# hr_monitor.net
KiCad netlist of a schematic drawn in EAGLE
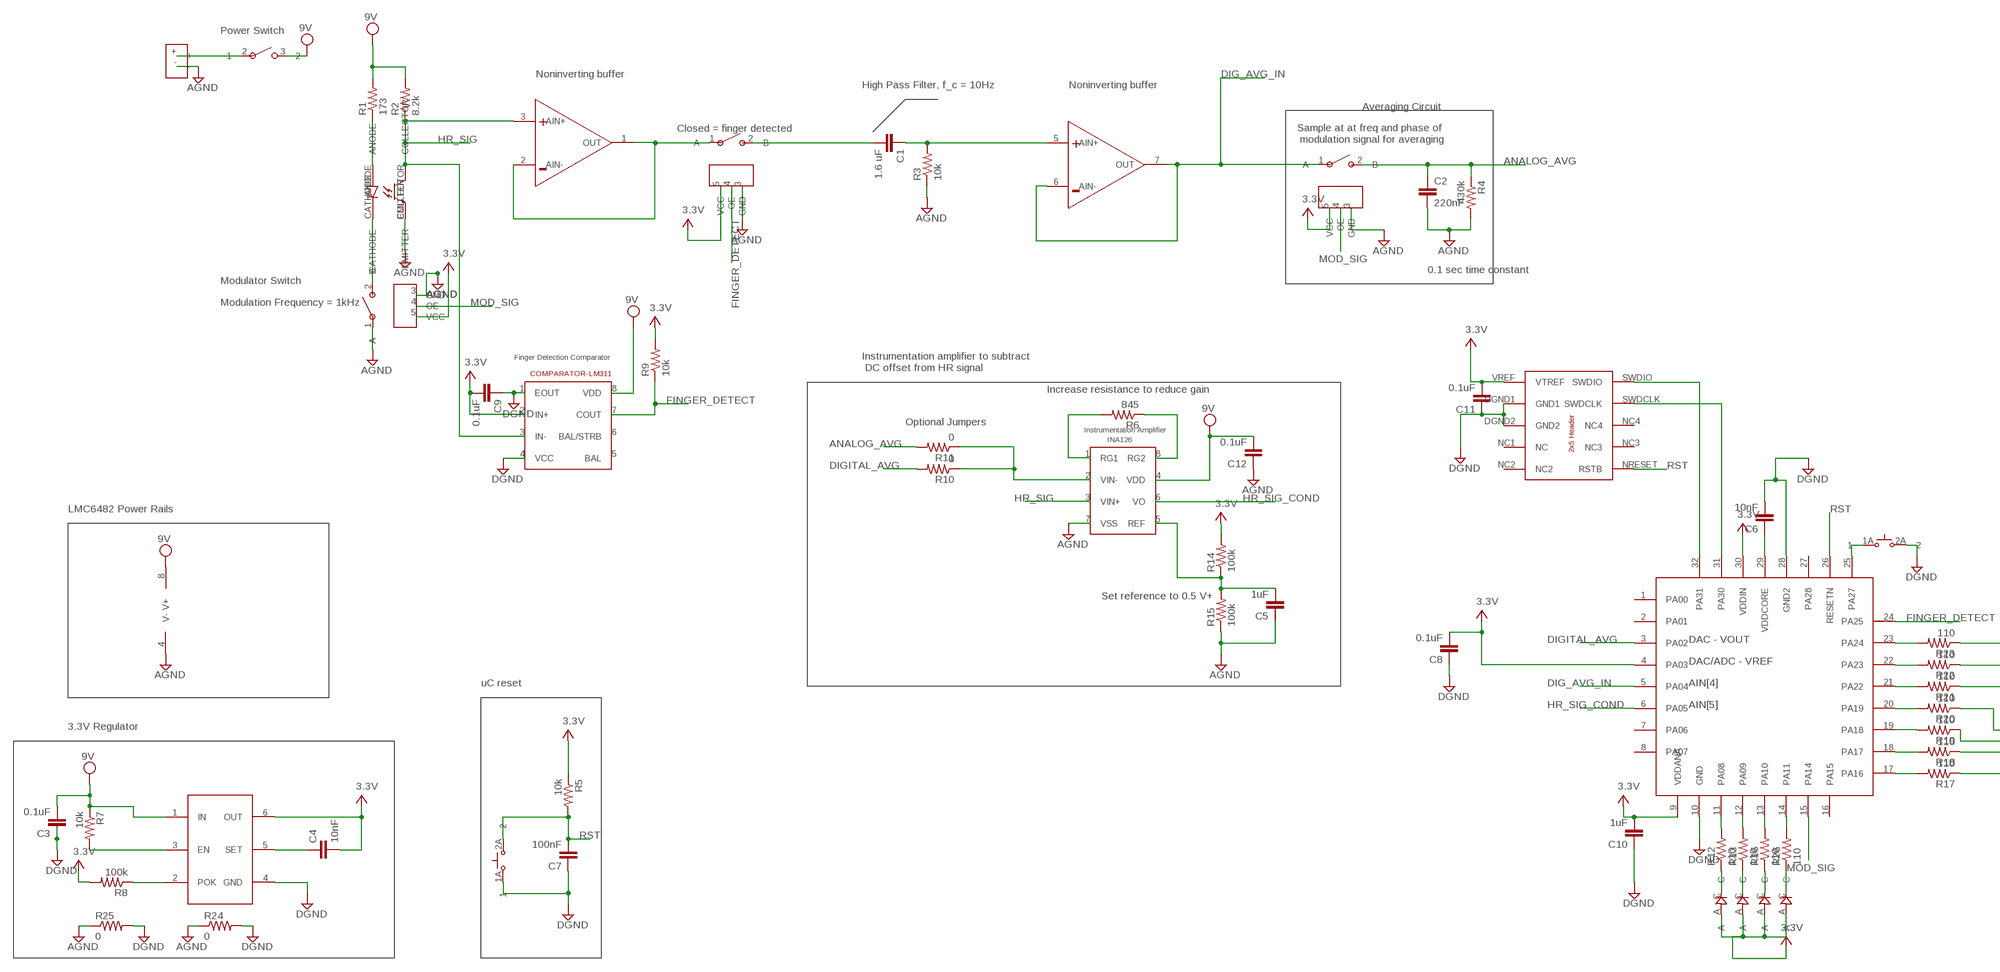
[diagram p0: schematic, sheet 1, part 1 of 2]
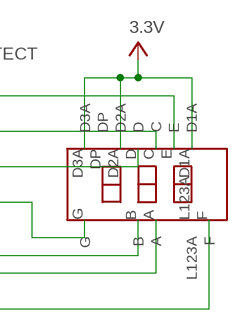
[diagram p1: schematic, sheet 1, part 2 of 2]

(export (version "E")
  (design (tool "Eeschema 10.0.6"))
  (components
    (comp (ref "C1")
      (value "1.6 uF")
      (footprint "eagle-import:C0805")
      (libsource (lib "eagle-import") (part "C-EUC0805"))
    )
    (comp (ref "C2")
      (value "220nF")
      (footprint "eagle-import:C0805")
      (libsource (lib "eagle-import") (part "C-EUC0805"))
    )
    (comp (ref "C3")
      (value "0.1uF")
      (footprint "eagle-import:C0805")
      (libsource (lib "eagle-import") (part "C-EUC0805"))
    )
    (comp (ref "C4")
      (value "10nF")
      (footprint "eagle-import:C0805")
      (libsource (lib "eagle-import") (part "C-EUC0805"))
    )
    (comp (ref "C5")
      (value "1uF")
      (footprint "eagle-import:C0805")
      (libsource (lib "eagle-import") (part "C-EUC0805"))
    )
    (comp (ref "C6")
      (value "10nF")
      (footprint "eagle-import:C0805")
      (libsource (lib "eagle-import") (part "C-EUC0805"))
    )
    (comp (ref "C7")
      (value "100nF")
      (footprint "eagle-import:C0805")
      (libsource (lib "eagle-import") (part "C-EUC0805"))
    )
    (comp (ref "C8")
      (value "0.1uF")
      (footprint "eagle-import:C0805")
      (libsource (lib "eagle-import") (part "C-EUC0805"))
    )
    (comp (ref "C9")
      (value "0.1uF")
      (footprint "eagle-import:C0805")
      (libsource (lib "eagle-import") (part "C-EUC0805"))
    )
    (comp (ref "C10")
      (value "1uF")
      (footprint "eagle-import:C0805")
      (libsource (lib "eagle-import") (part "C-EUC0805"))
    )
    (comp (ref "C11")
      (value "0.1uF")
      (footprint "eagle-import:C0805")
      (libsource (lib "eagle-import") (part "C-EUC0805"))
    )
    (comp (ref "C12")
      (value "0.1uF")
      (footprint "eagle-import:C0805")
      (libsource (lib "eagle-import") (part "C-EUC0805"))
    )
    (comp (ref "DBG1")
      (value "DEBUGHEAD")
      (footprint "eagle-import:DEBUGHEAD")
      (libsource (lib "eagle-import") (part "DEBUGHEAD"))
    )
    (comp (ref "R1")
      (value "173")
      (footprint "eagle-import:R0805")
      (libsource (lib "eagle-import") (part "R-US_R0805"))
    )
    (comp (ref "R2")
      (value "8.2k")
      (footprint "eagle-import:R0805")
      (libsource (lib "eagle-import") (part "R-US_R0805"))
    )
    (comp (ref "R3")
      (value "10k")
      (footprint "eagle-import:R0805")
      (libsource (lib "eagle-import") (part "R-US_R0805"))
    )
    (comp (ref "R4")
      (value "430k")
      (footprint "eagle-import:R0805")
      (libsource (lib "eagle-import") (part "R-US_R0805"))
    )
    (comp (ref "R5")
      (value "10k")
      (footprint "eagle-import:R0805")
      (libsource (lib "eagle-import") (part "R-US_R0805"))
    )
    (comp (ref "R6")
      (value "845")
      (footprint "eagle-import:R0805")
      (libsource (lib "eagle-import") (part "R-US_R0805"))
    )
    (comp (ref "R7")
      (value "10k")
      (footprint "eagle-import:R0805")
      (libsource (lib "eagle-import") (part "R-US_R0805"))
    )
    (comp (ref "R8")
      (value "100k")
      (footprint "eagle-import:R0805")
      (libsource (lib "eagle-import") (part "R-US_R0805"))
    )
    (comp (ref "R9")
      (value "10k")
      (footprint "eagle-import:R0805")
      (libsource (lib "eagle-import") (part "R-US_R0805"))
    )
    (comp (ref "R10")
      (value "0")
      (footprint "eagle-import:R0805")
      (libsource (lib "eagle-import") (part "R-US_R0805"))
    )
    (comp (ref "R11")
      (value "0")
      (footprint "eagle-import:R0805")
      (libsource (lib "eagle-import") (part "R-US_R0805"))
    )
    (comp (ref "R12")
      (value "110")
      (footprint "eagle-import:R0805")
      (libsource (lib "eagle-import") (part "R-US_R0805"))
    )
    (comp (ref "R13")
      (value "110")
      (footprint "eagle-import:R0805")
      (libsource (lib "eagle-import") (part "R-US_R0805"))
    )
    (comp (ref "R14")
      (value "100k")
      (footprint "eagle-import:R0805")
      (libsource (lib "eagle-import") (part "R-US_R0805"))
    )
    (comp (ref "R15")
      (value "100k")
      (footprint "eagle-import:R0805")
      (libsource (lib "eagle-import") (part "R-US_R0805"))
    )
    (comp (ref "R16")
      (value "110")
      (footprint "eagle-import:R0805")
      (libsource (lib "eagle-import") (part "R-US_R0805"))
    )
    (comp (ref "R17")
      (value "110")
      (footprint "eagle-import:R0805")
      (libsource (lib "eagle-import") (part "R-US_R0805"))
    )
    (comp (ref "R18")
      (value "110")
      (footprint "eagle-import:R0805")
      (libsource (lib "eagle-import") (part "R-US_R0805"))
    )
    (comp (ref "R19")
      (value "110")
      (footprint "eagle-import:R0805")
      (libsource (lib "eagle-import") (part "R-US_R0805"))
    )
    (comp (ref "R20")
      (value "110")
      (footprint "eagle-import:R0805")
      (libsource (lib "eagle-import") (part "R-US_R0805"))
    )
    (comp (ref "R21")
      (value "110")
      (footprint "eagle-import:R0805")
      (libsource (lib "eagle-import") (part "R-US_R0805"))
    )
    (comp (ref "R22")
      (value "110")
      (footprint "eagle-import:R0805")
      (libsource (lib "eagle-import") (part "R-US_R0805"))
    )
    (comp (ref "R23")
      (value "110")
      (footprint "eagle-import:R0805")
      (libsource (lib "eagle-import") (part "R-US_R0805"))
    )
    (comp (ref "R24")
      (value "0")
      (footprint "eagle-import:R0805")
      (libsource (lib "eagle-import") (part "R-US_R0805"))
    )
    (comp (ref "R25")
      (value "0")
      (footprint "eagle-import:R0805")
      (libsource (lib "eagle-import") (part "R-US_R0805"))
    )
    (comp (ref "R26")
      (value "110")
      (footprint "eagle-import:R0805")
      (libsource (lib "eagle-import") (part "R-US_R0805"))
    )
    (comp (ref "U$2")
      (value "SPST")
      (footprint "eagle-import:SOT23")
      (libsource (lib "eagle-import") (part "SPST"))
    )
    (comp (ref "U$3")
      (value "INA126")
      (footprint "eagle-import:SOIC-8")
      (libsource (lib "eagle-import") (part "INA126"))
    )
    (comp (ref "U$4")
      (value "LM311")
      (footprint "eagle-import:SOIC8")
      (libsource (lib "eagle-import") (part "LM311"))
    )
    (comp (ref "U$5")
      (value "SPST")
      (footprint "eagle-import:SOT23")
      (libsource (lib "eagle-import") (part "SPST"))
    )
    (comp (ref "U$6")
      (value "LMC6482")
      (footprint "eagle-import:SOIC8")
      (libsource (lib "eagle-import") (part "LMC6482"))
    )
    (comp (ref "U$7")
      (value "SPST")
      (footprint "eagle-import:SOT23")
      (libsource (lib "eagle-import") (part "SPST"))
    )
    (comp (ref "U$8")
      (value "SWITCHPUSHBUTTON")
      (footprint "eagle-import:KMR7-SWITCH")
      (libsource (lib "eagle-import") (part "SWITCHPUSHBUTTON"))
    )
    (comp (ref "U$9")
      (value "LED")
      (footprint "eagle-import:LED")
      (libsource (lib "eagle-import") (part "LED"))
    )
    (comp (ref "U$10")
      (value "3DIG-7SEG-DISPLAY")
      (footprint "eagle-import:3-DIGIT-7SEG")
      (libsource (lib "eagle-import") (part "3DIG-7SEG-DISPLAY"))
    )
    (comp (ref "U$11")
      (value "PWR-CONN")
      (footprint "eagle-import:THRU-HOLE-POWER")
      (libsource (lib "eagle-import") (part "PWR-CONN"))
    )
    (comp (ref "U$12")
      (value "SWITCH2")
      (footprint "eagle-import:DPDT-SLIDE-SWITCH")
      (libsource (lib "eagle-import") (part "SWITCH2"))
    )
    (comp (ref "U$13")
      (value "SWITCHPUSHBUTTON")
      (footprint "eagle-import:KMR7-SWITCH")
      (libsource (lib "eagle-import") (part "SWITCHPUSHBUTTON"))
    )
    (comp (ref "U$14")
      (value "LED")
      (footprint "eagle-import:LED")
      (libsource (lib "eagle-import") (part "LED"))
    )
    (comp (ref "U$15")
      (value "LED")
      (footprint "eagle-import:LED")
      (libsource (lib "eagle-import") (part "LED"))
    )
    (comp (ref "U$16")
      (value "LED")
      (footprint "eagle-import:LED")
      (libsource (lib "eagle-import") (part "LED"))
    )
    (comp (ref "U$17")
      (value "TCRT1000")
      (footprint "eagle-import:TCRT1000")
      (libsource (lib "eagle-import") (part "TCRT1000"))
    )
    (comp (ref "U1")
      (value "SAMD21E")
      (footprint "eagle-import:TQFP32-08")
      (libsource (lib "eagle-import") (part "SAMD21E"))
    )
    (comp (ref "U2")
      (value "3.3V_AS1363")
      (footprint "eagle-import:SOT23-6")
      (libsource (lib "eagle-import") (part "3.3V_AS1363"))
    )
  )
  (nets
    (net (code "1") (name "/ANALOG_AVG") (class "Default")
      (node (ref "C2") (pin "1") (pinfunction "1_1") (pintype "passive"))
      (node (ref "R11") (pin "2") (pinfunction "2_2") (pintype "passive"))
      (node (ref "R4") (pin "1") (pinfunction "1_1") (pintype "passive"))
      (node (ref "U$7") (pin "2") (pinfunction "B_2") (pintype "bidirectional"))
    )
    (net (code "2") (name "/DIGITAL_AVG") (class "Default")
      (node (ref "R10") (pin "2") (pinfunction "2_2") (pintype "passive"))
      (node (ref "U1") (pin "3") (pinfunction "PA02_3") (pintype "bidirectional"))
    )
    (net (code "3") (name "/DIG_AVG_IN") (class "Default")
      (node (ref "U$6") (pin "6") (pinfunction "AIN-_6") (pintype "bidirectional"))
      (node (ref "U$6") (pin "7") (pinfunction "OUT_7") (pintype "bidirectional"))
      (node (ref "U$7") (pin "1") (pinfunction "A_1") (pintype "bidirectional"))
      (node (ref "U1") (pin "5") (pinfunction "PA04_5") (pintype "bidirectional"))
    )
    (net (code "4") (name "/FINGER_DETECT") (class "Default")
      (node (ref "R9") (pin "1") (pinfunction "1_1") (pintype "passive"))
      (node (ref "U$2") (pin "4") (pinfunction "OE_4") (pintype "bidirectional"))
      (node (ref "U$4") (pin "7") (pinfunction "COUT_7") (pintype "bidirectional"))
      (node (ref "U1") (pin "24") (pinfunction "PA25_24") (pintype "bidirectional"))
    )
    (net (code "5") (name "/HR_SIG") (class "Default")
      (node (ref "R2") (pin "1") (pinfunction "1_1") (pintype "passive"))
      (node (ref "U$17") (pin "COLLECTOR") (pinfunction "COLLECTOR_COLLECTOR") (pintype "bidirectional"))
      (node (ref "U$3") (pin "3") (pinfunction "VIN+_3") (pintype "bidirectional"))
      (node (ref "U$4") (pin "3") (pinfunction "IN-_3") (pintype "bidirectional"))
      (node (ref "U$6") (pin "3") (pinfunction "AIN+_3") (pintype "bidirectional"))
    )
    (net (code "6") (name "/HR_SIG_COND") (class "Default")
      (node (ref "U$3") (pin "6") (pinfunction "VO_6") (pintype "bidirectional"))
      (node (ref "U1") (pin "6") (pinfunction "PA05_6") (pintype "bidirectional"))
    )
    (net (code "7") (name "/MOD_SIG") (class "Default")
      (node (ref "U$5") (pin "4") (pinfunction "OE_4") (pintype "bidirectional"))
      (node (ref "U$7") (pin "4") (pinfunction "OE_4") (pintype "bidirectional"))
      (node (ref "U1") (pin "15") (pinfunction "PA14_15") (pintype "bidirectional"))
    )
    (net (code "8") (name "/RST") (class "Default")
      (node (ref "C7") (pin "2") (pinfunction "2_2") (pintype "passive"))
      (node (ref "DBG1") (pin "NRESET") (pinfunction "RSTB_NRESET") (pintype "bidirectional"))
      (node (ref "R5") (pin "2") (pinfunction "2_2") (pintype "passive"))
      (node (ref "U$8") (pin "2A") (pinfunction "2_2A") (pintype "bidirectional"))
      (node (ref "U1") (pin "26") (pinfunction "RESETN_26") (pintype "bidirectional"))
    )
    (net (code "9") (name "3.3V") (class "Default")
      (node (ref "C10") (pin "2") (pinfunction "2_2") (pintype "passive"))
      (node (ref "C11") (pin "2") (pinfunction "2_2") (pintype "passive"))
      (node (ref "C4") (pin "2") (pinfunction "2_2") (pintype "passive"))
      (node (ref "C8") (pin "2") (pinfunction "2_2") (pintype "passive"))
      (node (ref "C9") (pin "2") (pinfunction "2_2") (pintype "passive"))
      (node (ref "DBG1") (pin "VREF") (pinfunction "VTREF_VREF") (pintype "bidirectional"))
      (node (ref "R14") (pin "2") (pinfunction "2_2") (pintype "passive"))
      (node (ref "R5") (pin "1") (pinfunction "1_1") (pintype "passive"))
      (node (ref "R8") (pin "2") (pinfunction "2_2") (pintype "passive"))
      (node (ref "R9") (pin "2") (pinfunction "2_2") (pintype "passive"))
      (node (ref "U$10") (pin "D1A") (pinfunction "D1A_D1A") (pintype "bidirectional"))
      (node (ref "U$10") (pin "D2A") (pinfunction "D2A_D2A") (pintype "bidirectional"))
      (node (ref "U$10") (pin "D3A") (pinfunction "D3A_D3A") (pintype "bidirectional"))
      (node (ref "U$14") (pin "A") (pinfunction "A_A") (pintype "bidirectional"))
      (node (ref "U$15") (pin "A") (pinfunction "A_A") (pintype "bidirectional"))
      (node (ref "U$16") (pin "A") (pinfunction "A_A") (pintype "bidirectional"))
      (node (ref "U$2") (pin "5") (pinfunction "VCC_5") (pintype "bidirectional"))
      (node (ref "U$4") (pin "2") (pinfunction "IN+_2") (pintype "bidirectional"))
      (node (ref "U$5") (pin "5") (pinfunction "VCC_5") (pintype "bidirectional"))
      (node (ref "U$7") (pin "5") (pinfunction "VCC_5") (pintype "bidirectional"))
      (node (ref "U$9") (pin "A") (pinfunction "A_A") (pintype "bidirectional"))
      (node (ref "U1") (pin "30") (pinfunction "VDDIN_30") (pintype "bidirectional"))
      (node (ref "U1") (pin "4") (pinfunction "PA03_4") (pintype "bidirectional"))
      (node (ref "U1") (pin "9") (pinfunction "VDDANA_9") (pintype "bidirectional"))
      (node (ref "U2") (pin "6") (pinfunction "OUT_6") (pintype "bidirectional"))
    )
    (net (code "10") (name "9V") (class "Default")
      (node (ref "C12") (pin "2") (pinfunction "2_2") (pintype "passive"))
      (node (ref "C3") (pin "2") (pinfunction "2_2") (pintype "passive"))
      (node (ref "R1") (pin "2") (pinfunction "2_2") (pintype "passive"))
      (node (ref "R2") (pin "2") (pinfunction "2_2") (pintype "passive"))
      (node (ref "R7") (pin "1") (pinfunction "1_1") (pintype "passive"))
      (node (ref "U$12") (pin "3") (pinfunction "2_3") (pintype "bidirectional"))
      (node (ref "U$3") (pin "4") (pinfunction "VDD_4") (pintype "bidirectional"))
      (node (ref "U$4") (pin "8") (pinfunction "VDD_8") (pintype "bidirectional"))
      (node (ref "U$6") (pin "8") (pinfunction "V+_8") (pintype "bidirectional"))
      (node (ref "U2") (pin "1") (pinfunction "IN_1") (pintype "bidirectional"))
    )
    (net (code "11") (name "AGND") (class "Default")
      (node (ref "C12") (pin "1") (pinfunction "1_1") (pintype "passive"))
      (node (ref "C2") (pin "2") (pinfunction "2_2") (pintype "passive"))
      (node (ref "C5") (pin "1") (pinfunction "1_1") (pintype "passive"))
      (node (ref "R15") (pin "1") (pinfunction "1_1") (pintype "passive"))
      (node (ref "R24") (pin "1") (pinfunction "1_1") (pintype "passive"))
      (node (ref "R25") (pin "1") (pinfunction "1_1") (pintype "passive"))
      (node (ref "R3") (pin "1") (pinfunction "1_1") (pintype "passive"))
      (node (ref "R4") (pin "2") (pinfunction "2_2") (pintype "passive"))
      (node (ref "U$11") (pin "-") (pinfunction "-_-") (pintype "bidirectional"))
      (node (ref "U$17") (pin "EMITTER") (pinfunction "EMITTER_EMITTER") (pintype "bidirectional"))
      (node (ref "U$2") (pin "3") (pinfunction "GND_3") (pintype "bidirectional"))
      (node (ref "U$3") (pin "7") (pinfunction "VSS_7") (pintype "bidirectional"))
      (node (ref "U$5") (pin "1") (pinfunction "A_1") (pintype "bidirectional"))
      (node (ref "U$5") (pin "3") (pinfunction "GND_3") (pintype "bidirectional"))
      (node (ref "U$6") (pin "4") (pinfunction "V-_4") (pintype "bidirectional"))
      (node (ref "U$7") (pin "3") (pinfunction "GND_3") (pintype "bidirectional"))
    )
    (net (code "12") (name "DGND") (class "Default")
      (node (ref "C10") (pin "1") (pinfunction "1_1") (pintype "passive"))
      (node (ref "C11") (pin "1") (pinfunction "1_1") (pintype "passive"))
      (node (ref "C3") (pin "1") (pinfunction "1_1") (pintype "passive"))
      (node (ref "C6") (pin "2") (pinfunction "2_2") (pintype "passive"))
      (node (ref "C7") (pin "1") (pinfunction "1_1") (pintype "passive"))
      (node (ref "C8") (pin "1") (pinfunction "1_1") (pintype "passive"))
      (node (ref "C9") (pin "1") (pinfunction "1_1") (pintype "passive"))
      (node (ref "DBG1") (pin "DGND1") (pinfunction "GND1_DGND1") (pintype "bidirectional"))
      (node (ref "DBG1") (pin "DGND2") (pinfunction "GND2_DGND2") (pintype "bidirectional"))
      (node (ref "R24") (pin "2") (pinfunction "2_2") (pintype "passive"))
      (node (ref "R25") (pin "2") (pinfunction "2_2") (pintype "passive"))
      (node (ref "U$13") (pin "2A") (pinfunction "2_2A") (pintype "bidirectional"))
      (node (ref "U$4") (pin "1") (pinfunction "EOUT_1") (pintype "bidirectional"))
      (node (ref "U$4") (pin "4") (pinfunction "VCC_4") (pintype "bidirectional"))
      (node (ref "U$8") (pin "1A") (pinfunction "1_1A") (pintype "bidirectional"))
      (node (ref "U1") (pin "10") (pinfunction "GND_10") (pintype "bidirectional"))
      (node (ref "U1") (pin "28") (pinfunction "GND2_28") (pintype "bidirectional"))
      (node (ref "U2") (pin "4") (pinfunction "GND_4") (pintype "bidirectional"))
    )
    (net (code "13") (name "Net-(R1-Pad1)") (class "Default")
      (node (ref "R1") (pin "1") (pinfunction "1_1") (pintype "passive"))
      (node (ref "U$17") (pin "ANODE") (pinfunction "ANODE_ANODE") (pintype "bidirectional"))
    )
    (net (code "14") (name "Net-(R12-Pad1)") (class "Default")
      (node (ref "R12") (pin "1") (pinfunction "1_1") (pintype "passive"))
      (node (ref "U$9") (pin "C") (pinfunction "C_C") (pintype "bidirectional"))
    )
    (net (code "15") (name "Net-(R13-Pad1)") (class "Default")
      (node (ref "R13") (pin "1") (pinfunction "1_1") (pintype "passive"))
      (node (ref "U$14") (pin "C") (pinfunction "C_C") (pintype "bidirectional"))
    )
    (net (code "16") (name "Net-(R16-Pad1)") (class "Default")
      (node (ref "R16") (pin "1") (pinfunction "1_1") (pintype "passive"))
      (node (ref "U$15") (pin "C") (pinfunction "C_C") (pintype "bidirectional"))
    )
    (net (code "17") (name "Net-(R17-Pad1)") (class "Default")
      (node (ref "R17") (pin "1") (pinfunction "1_1") (pintype "passive"))
      (node (ref "U$10") (pin "F") (pinfunction "F_F") (pintype "bidirectional"))
    )
    (net (code "18") (name "Net-(R18-Pad1)") (class "Default")
      (node (ref "R18") (pin "1") (pinfunction "1_1") (pintype "passive"))
      (node (ref "U$10") (pin "A") (pinfunction "A_A") (pintype "bidirectional"))
    )
    (net (code "19") (name "Net-(R19-Pad1)") (class "Default")
      (node (ref "R19") (pin "1") (pinfunction "1_1") (pintype "passive"))
      (node (ref "U$10") (pin "B") (pinfunction "B_B") (pintype "bidirectional"))
    )
    (net (code "20") (name "Net-(R20-Pad1)") (class "Default")
      (node (ref "R20") (pin "1") (pinfunction "1_1") (pintype "passive"))
      (node (ref "U$10") (pin "G") (pinfunction "G_G") (pintype "bidirectional"))
    )
    (net (code "21") (name "Net-(R21-Pad1)") (class "Default")
      (node (ref "R21") (pin "1") (pinfunction "1_1") (pintype "passive"))
      (node (ref "U$10") (pin "D") (pinfunction "D_D") (pintype "bidirectional"))
    )
    (net (code "22") (name "Net-(R22-Pad1)") (class "Default")
      (node (ref "R22") (pin "1") (pinfunction "1_1") (pintype "passive"))
      (node (ref "U$10") (pin "C") (pinfunction "C_C") (pintype "bidirectional"))
    )
    (net (code "23") (name "Net-(R23-Pad1)") (class "Default")
      (node (ref "R23") (pin "1") (pinfunction "1_1") (pintype "passive"))
      (node (ref "U$10") (pin "E") (pinfunction "E_E") (pintype "bidirectional"))
    )
    (net (code "24") (name "Net-(R26-Pad1)") (class "Default")
      (node (ref "R26") (pin "1") (pinfunction "1_1") (pintype "passive"))
      (node (ref "U$16") (pin "C") (pinfunction "C_C") (pintype "bidirectional"))
    )
    (net (code "25") (name "Net-(U$2-A)") (class "Default")
      (node (ref "U$2") (pin "1") (pinfunction "A_1") (pintype "bidirectional"))
      (node (ref "U$6") (pin "1") (pinfunction "OUT_1") (pintype "bidirectional"))
      (node (ref "U$6") (pin "2") (pinfunction "AIN-_2") (pintype "bidirectional"))
    )
    (net (code "26") (name "Net-(U$2-B)") (class "Default")
      (node (ref "C1") (pin "2") (pinfunction "2_2") (pintype "passive"))
      (node (ref "U$2") (pin "2") (pinfunction "B_2") (pintype "bidirectional"))
    )
    (net (code "27") (name "Net-(U$3-REF)") (class "Default")
      (node (ref "C5") (pin "2") (pinfunction "2_2") (pintype "passive"))
      (node (ref "R14") (pin "1") (pinfunction "1_1") (pintype "passive"))
      (node (ref "R15") (pin "2") (pinfunction "2_2") (pintype "passive"))
      (node (ref "U$3") (pin "5") (pinfunction "REF_5") (pintype "bidirectional"))
    )
    (net (code "28") (name "Net-(U$3-RG1)") (class "Default")
      (node (ref "R6") (pin "2") (pinfunction "2_2") (pintype "passive"))
      (node (ref "U$3") (pin "1") (pinfunction "RG1_1") (pintype "bidirectional"))
    )
    (net (code "29") (name "Net-(U$3-RG2)") (class "Default")
      (node (ref "R6") (pin "1") (pinfunction "1_1") (pintype "passive"))
      (node (ref "U$3") (pin "8") (pinfunction "RG2_8") (pintype "bidirectional"))
    )
    (net (code "30") (name "Net-(U$3-VIN-)") (class "Default")
      (node (ref "R10") (pin "1") (pinfunction "1_1") (pintype "passive"))
      (node (ref "R11") (pin "1") (pinfunction "1_1") (pintype "passive"))
      (node (ref "U$3") (pin "2") (pinfunction "VIN-_2") (pintype "bidirectional"))
    )
    (net (code "31") (name "Net-(U$5-B)") (class "Default")
      (node (ref "U$17") (pin "CATHODE") (pinfunction "CATHODE_CATHODE") (pintype "bidirectional"))
      (node (ref "U$5") (pin "2") (pinfunction "B_2") (pintype "bidirectional"))
    )
    (net (code "32") (name "Net-(U$6B-AIN+)") (class "Default")
      (node (ref "C1") (pin "1") (pinfunction "1_1") (pintype "passive"))
      (node (ref "R3") (pin "2") (pinfunction "2_2") (pintype "passive"))
      (node (ref "U$6") (pin "5") (pinfunction "AIN+_5") (pintype "bidirectional"))
    )
    (net (code "33") (name "Net-(U$12-1)") (class "Default")
      (node (ref "U$11") (pin "+") (pinfunction "+_+") (pintype "bidirectional"))
      (node (ref "U$12") (pin "2") (pinfunction "1_2") (pintype "bidirectional"))
    )
    (net (code "34") (name "Net-(U$13-1)") (class "Default")
      (node (ref "U$13") (pin "1A") (pinfunction "1_1A") (pintype "bidirectional"))
      (node (ref "U1") (pin "25") (pinfunction "PA27_25") (pintype "bidirectional"))
    )
    (net (code "35") (name "Net-(U1-PA08)") (class "Default")
      (node (ref "R12") (pin "2") (pinfunction "2_2") (pintype "passive"))
      (node (ref "U1") (pin "11") (pinfunction "PA08_11") (pintype "bidirectional"))
    )
    (net (code "36") (name "Net-(U1-PA09)") (class "Default")
      (node (ref "R13") (pin "2") (pinfunction "2_2") (pintype "passive"))
      (node (ref "U1") (pin "12") (pinfunction "PA09_12") (pintype "bidirectional"))
    )
    (net (code "37") (name "Net-(U1-PA10)") (class "Default")
      (node (ref "R16") (pin "2") (pinfunction "2_2") (pintype "passive"))
      (node (ref "U1") (pin "13") (pinfunction "PA10_13") (pintype "bidirectional"))
    )
    (net (code "38") (name "Net-(U1-PA11)") (class "Default")
      (node (ref "R26") (pin "2") (pinfunction "2_2") (pintype "passive"))
      (node (ref "U1") (pin "14") (pinfunction "PA11_14") (pintype "bidirectional"))
    )
    (net (code "39") (name "Net-(U1-PA16)") (class "Default")
      (node (ref "R17") (pin "2") (pinfunction "2_2") (pintype "passive"))
      (node (ref "U1") (pin "17") (pinfunction "PA16_17") (pintype "bidirectional"))
    )
    (net (code "40") (name "Net-(U1-PA17)") (class "Default")
      (node (ref "R18") (pin "2") (pinfunction "2_2") (pintype "passive"))
      (node (ref "U1") (pin "18") (pinfunction "PA17_18") (pintype "bidirectional"))
    )
    (net (code "41") (name "Net-(U1-PA18)") (class "Default")
      (node (ref "R19") (pin "2") (pinfunction "2_2") (pintype "passive"))
      (node (ref "U1") (pin "19") (pinfunction "PA18_19") (pintype "bidirectional"))
    )
    (net (code "42") (name "Net-(U1-PA19)") (class "Default")
      (node (ref "R20") (pin "2") (pinfunction "2_2") (pintype "passive"))
      (node (ref "U1") (pin "20") (pinfunction "PA19_20") (pintype "bidirectional"))
    )
    (net (code "43") (name "Net-(U1-PA22)") (class "Default")
      (node (ref "R21") (pin "2") (pinfunction "2_2") (pintype "passive"))
      (node (ref "U1") (pin "21") (pinfunction "PA22_21") (pintype "bidirectional"))
    )
    (net (code "44") (name "Net-(U1-PA23)") (class "Default")
      (node (ref "R22") (pin "2") (pinfunction "2_2") (pintype "passive"))
      (node (ref "U1") (pin "22") (pinfunction "PA23_22") (pintype "bidirectional"))
    )
    (net (code "45") (name "Net-(U1-PA24)") (class "Default")
      (node (ref "R23") (pin "2") (pinfunction "2_2") (pintype "passive"))
      (node (ref "U1") (pin "23") (pinfunction "PA24_23") (pintype "bidirectional"))
    )
    (net (code "46") (name "Net-(U1-PA30)") (class "Default")
      (node (ref "DBG1") (pin "SWDCLK") (pinfunction "SWDCLK_SWDCLK") (pintype "bidirectional"))
      (node (ref "U1") (pin "31") (pinfunction "PA30_31") (pintype "bidirectional"))
    )
    (net (code "47") (name "Net-(U1-PA31)") (class "Default")
      (node (ref "DBG1") (pin "SWDIO") (pinfunction "SWDIO_SWDIO") (pintype "bidirectional"))
      (node (ref "U1") (pin "32") (pinfunction "PA31_32") (pintype "bidirectional"))
    )
    (net (code "48") (name "Net-(U1-VDDCORE)") (class "Default")
      (node (ref "C6") (pin "1") (pinfunction "1_1") (pintype "passive"))
      (node (ref "U1") (pin "29") (pinfunction "VDDCORE_29") (pintype "bidirectional"))
    )
    (net (code "49") (name "Net-(U2-EN)") (class "Default")
      (node (ref "R7") (pin "2") (pinfunction "2_2") (pintype "passive"))
      (node (ref "U2") (pin "3") (pinfunction "EN_3") (pintype "bidirectional"))
    )
    (net (code "50") (name "Net-(U2-POK)") (class "Default")
      (node (ref "R8") (pin "1") (pinfunction "1_1") (pintype "passive"))
      (node (ref "U2") (pin "2") (pinfunction "POK_2") (pintype "bidirectional"))
    )
    (net (code "51") (name "Net-(U2-SET)") (class "Default")
      (node (ref "C4") (pin "1") (pinfunction "1_1") (pintype "passive"))
      (node (ref "U2") (pin "5") (pinfunction "SET_5") (pintype "bidirectional"))
    )
    (net (code "52") (name "unconnected-(DBG1-NC-PadNC1)") (class "Default")
      (node (ref "DBG1") (pin "NC1") (pinfunction "NC_NC1") (pintype "bidirectional"))
    )
    (net (code "53") (name "unconnected-(DBG1-PadNC2)") (class "Default")
      (node (ref "DBG1") (pin "NC2") (pinfunction "NC2_NC2") (pintype "bidirectional"))
    )
    (net (code "54") (name "unconnected-(DBG1-PadNC3)") (class "Default")
      (node (ref "DBG1") (pin "NC3") (pinfunction "NC3_NC3") (pintype "bidirectional"))
    )
    (net (code "55") (name "unconnected-(DBG1-PadNC4)") (class "Default")
      (node (ref "DBG1") (pin "NC4") (pinfunction "NC4_NC4") (pintype "bidirectional"))
    )
    (net (code "56") (name "unconnected-(U$4-BAL-Pad5)") (class "Default")
      (node (ref "U$4") (pin "5") (pinfunction "BAL_5") (pintype "bidirectional"))
    )
    (net (code "57") (name "unconnected-(U$4-BAL{slash}STRB-Pad6)") (class "Default")
      (node (ref "U$4") (pin "6") (pinfunction "BAL/STRB_6") (pintype "bidirectional"))
    )
    (net (code "58") (name "unconnected-(U$10-PadDP)") (class "Default")
      (node (ref "U$10") (pin "DP") (pinfunction "DP_DP") (pintype "bidirectional"))
    )
    (net (code "59") (name "unconnected-(U$10-PadL123A)") (class "Default")
      (node (ref "U$10") (pin "L123A") (pinfunction "L123A_L123A") (pintype "bidirectional"))
    )
    (net (code "60") (name "unconnected-(U1-PA00-Pad1)") (class "Default")
      (node (ref "U1") (pin "1") (pinfunction "PA00_1") (pintype "bidirectional"))
    )
    (net (code "61") (name "unconnected-(U1-PA01-Pad2)") (class "Default")
      (node (ref "U1") (pin "2") (pinfunction "PA01_2") (pintype "bidirectional"))
    )
    (net (code "62") (name "unconnected-(U1-PA06-Pad7)") (class "Default")
      (node (ref "U1") (pin "7") (pinfunction "PA06_7") (pintype "bidirectional"))
    )
    (net (code "63") (name "unconnected-(U1-PA07-Pad8)") (class "Default")
      (node (ref "U1") (pin "8") (pinfunction "PA07_8") (pintype "bidirectional"))
    )
    (net (code "64") (name "unconnected-(U1-PA15-Pad16)") (class "Default")
      (node (ref "U1") (pin "16") (pinfunction "PA15_16") (pintype "bidirectional"))
    )
    (net (code "65") (name "unconnected-(U1-PA28-Pad27)") (class "Default")
      (node (ref "U1") (pin "27") (pinfunction "PA28_27") (pintype "bidirectional"))
    )
  )
)
